# Wireless_Modular_Burn_Board.net
KiCad netlist of a schematic drawn in EAGLE
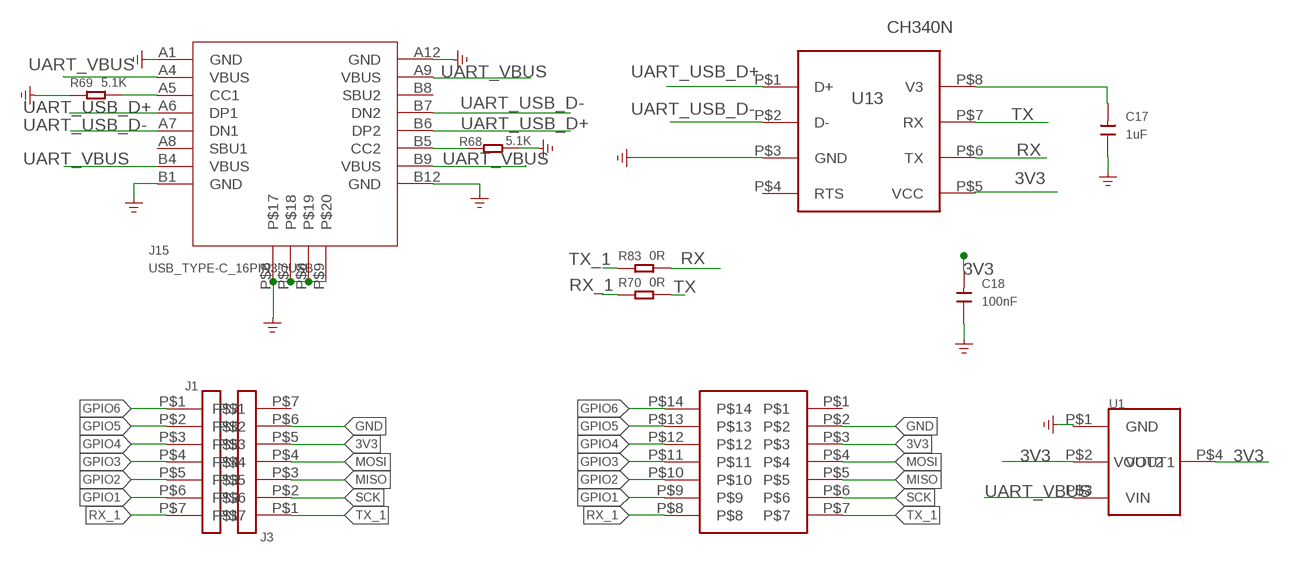
[diagram p0: schematic, sheet 1]

(export (version "E")
  (design (tool "Eeschema 10.0.6"))
  (components
    (comp (ref "C17")
      (value "1uF")
      (footprint "eagle-import:0603")
      (libsource (lib "eagle-import") (part "C0603"))
    )
    (comp (ref "C18")
      (value "100nF")
      (footprint "eagle-import:0603")
      (libsource (lib "eagle-import") (part "C0603"))
    )
    (comp (ref "J1")
      (value "2.54MM-7P")
      (footprint "eagle-import:2.54MM-7P")
      (libsource (lib "eagle-import") (part "2.54MM-7P"))
    )
    (comp (ref "J2")
      (value "SMT-2.54MM-7P")
      (footprint "eagle-import:SMT-2.54MM-7P")
      (libsource (lib "eagle-import") (part "SMT-2.54MM-7P"))
    )
    (comp (ref "J3")
      (value "2.54MM-7P")
      (footprint "eagle-import:2.54MM-7P")
      (libsource (lib "eagle-import") (part "2.54MM-7P"))
    )
    (comp (ref "J15")
      (value "USB_TYPE-C_16PIN3.0USB")
      (footprint "eagle-import:KEVIN_3.0TYPEC-SMD")
      (libsource (lib "eagle-import") (part "USB_TYPE-C_16PIN3.0USB"))
    )
    (comp (ref "R68")
      (value "5.1K")
      (footprint "eagle-import:DISCRETE_R0603")
      (libsource (lib "eagle-import") (part "DISCRETE_R-0603"))
    )
    (comp (ref "R69")
      (value "5.1K")
      (footprint "eagle-import:DISCRETE_R0603")
      (libsource (lib "eagle-import") (part "DISCRETE_R-0603"))
    )
    (comp (ref "R70")
      (value "0R")
      (footprint "eagle-import:DISCRETE_R0603")
      (libsource (lib "eagle-import") (part "DISCRETE_R-0603"))
    )
    (comp (ref "R83")
      (value "0R")
      (footprint "eagle-import:DISCRETE_R0603")
      (libsource (lib "eagle-import") (part "DISCRETE_R-0603"))
    )
    (comp (ref "U1")
      (value "AMS1117-3V3")
      (footprint "eagle-import:SOT-223")
      (libsource (lib "eagle-import") (part "AMS1117-3V3"))
    )
    (comp (ref "U13")
      (value "CH340N")
      (footprint "eagle-import:SOP8")
      (libsource (lib "eagle-import") (part "CH340NSOP-8"))
    )
  )
  (nets
    (net (code "1") (name "/RX") (class "Default")
      (node (ref "R83") (pin "2") (pinfunction "2_2") (pintype "passive"))
      (node (ref "U13") (pin "P$6") (pinfunction "TX_P$6") (pintype "bidirectional"))
    )
    (net (code "2") (name "/TX") (class "Default")
      (node (ref "R70") (pin "2") (pinfunction "2_2") (pintype "passive"))
      (node (ref "U13") (pin "P$7") (pinfunction "RX_P$7") (pintype "bidirectional"))
    )
    (net (code "3") (name "/UART_USB_D+") (class "Default")
      (node (ref "J15") (pin "A6") (pinfunction "DP1_A6") (pintype "bidirectional"))
      (node (ref "J15") (pin "B6") (pinfunction "DP2_B6") (pintype "bidirectional"))
      (node (ref "U13") (pin "P$1") (pinfunction "D+_P$1") (pintype "bidirectional"))
    )
    (net (code "4") (name "/UART_USB_D-") (class "Default")
      (node (ref "J15") (pin "A7") (pinfunction "DN1_A7") (pintype "bidirectional"))
      (node (ref "J15") (pin "B7") (pinfunction "DN2_B7") (pintype "bidirectional"))
      (node (ref "U13") (pin "P$2") (pinfunction "D-_P$2") (pintype "bidirectional"))
    )
    (net (code "5") (name "/UART_VBUS") (class "Default")
      (node (ref "J15") (pin "A4") (pinfunction "VBUS_A4") (pintype "bidirectional"))
      (node (ref "J15") (pin "A9") (pinfunction "VBUS_A9") (pintype "bidirectional"))
      (node (ref "J15") (pin "B4") (pinfunction "VBUS_B4") (pintype "bidirectional"))
      (node (ref "J15") (pin "B9") (pinfunction "VBUS_B9") (pintype "bidirectional"))
      (node (ref "U1") (pin "P$3") (pinfunction "VIN_P$3") (pintype "bidirectional"))
    )
    (net (code "6") (name "3V3") (class "Default")
      (node (ref "C18") (pin "2") (pinfunction "2_2") (pintype "passive"))
      (node (ref "J2") (pin "P$3") (pinfunction "P$3_P$3") (pintype "bidirectional"))
      (node (ref "J3") (pin "P$5") (pinfunction "P$5_P$5") (pintype "bidirectional"))
      (node (ref "U1") (pin "P$2") (pinfunction "VOUT1_P$2") (pintype "bidirectional"))
      (node (ref "U1") (pin "P$4") (pinfunction "VOUT2_P$4") (pintype "bidirectional"))
      (node (ref "U13") (pin "P$5") (pinfunction "VCC_P$5") (pintype "bidirectional"))
    )
    (net (code "7") (name "GND") (class "Default")
      (node (ref "C17") (pin "1") (pinfunction "1_1") (pintype "passive"))
      (node (ref "C18") (pin "1") (pinfunction "1_1") (pintype "passive"))
      (node (ref "J15") (pin "A1") (pinfunction "GND_A1") (pintype "bidirectional"))
      (node (ref "J15") (pin "A12") (pinfunction "GND_A12") (pintype "bidirectional"))
      (node (ref "J15") (pin "B1") (pinfunction "GND_B1") (pintype "bidirectional"))
      (node (ref "J15") (pin "B12") (pinfunction "GND_B12") (pintype "bidirectional"))
      (node (ref "J15") (pin "P$6") (pinfunction "P$17_P$6") (pintype "bidirectional"))
      (node (ref "J15") (pin "P$7") (pinfunction "P$18_P$7") (pintype "bidirectional"))
      (node (ref "J15") (pin "P$8") (pinfunction "P$19_P$8") (pintype "bidirectional"))
      (node (ref "J15") (pin "P$9") (pinfunction "P$20_P$9") (pintype "bidirectional"))
      (node (ref "J2") (pin "P$2") (pinfunction "P$2_P$2") (pintype "bidirectional"))
      (node (ref "J3") (pin "P$6") (pinfunction "P$6_P$6") (pintype "bidirectional"))
      (node (ref "R68") (pin "2") (pinfunction "2_2") (pintype "passive"))
      (node (ref "R69") (pin "1") (pinfunction "1_1") (pintype "passive"))
      (node (ref "U1") (pin "P$1") (pinfunction "GND_P$1") (pintype "bidirectional"))
      (node (ref "U13") (pin "P$3") (pinfunction "GND_P$3") (pintype "bidirectional"))
    )
    (net (code "8") (name "GPIO1") (class "Default")
      (node (ref "J1") (pin "P$6") (pinfunction "P$6_P$6") (pintype "bidirectional"))
      (node (ref "J2") (pin "P$9") (pinfunction "P$9_P$9") (pintype "bidirectional"))
    )
    (net (code "9") (name "GPIO2") (class "Default")
      (node (ref "J1") (pin "P$5") (pinfunction "P$5_P$5") (pintype "bidirectional"))
      (node (ref "J2") (pin "P$10") (pinfunction "P$10_P$10") (pintype "bidirectional"))
    )
    (net (code "10") (name "GPIO3") (class "Default")
      (node (ref "J1") (pin "P$4") (pinfunction "P$4_P$4") (pintype "bidirectional"))
      (node (ref "J2") (pin "P$11") (pinfunction "P$11_P$11") (pintype "bidirectional"))
    )
    (net (code "11") (name "GPIO4") (class "Default")
      (node (ref "J1") (pin "P$3") (pinfunction "P$3_P$3") (pintype "bidirectional"))
      (node (ref "J2") (pin "P$12") (pinfunction "P$12_P$12") (pintype "bidirectional"))
    )
    (net (code "12") (name "GPIO5") (class "Default")
      (node (ref "J1") (pin "P$2") (pinfunction "P$2_P$2") (pintype "bidirectional"))
      (node (ref "J2") (pin "P$13") (pinfunction "P$13_P$13") (pintype "bidirectional"))
    )
    (net (code "13") (name "GPIO6") (class "Default")
      (node (ref "J1") (pin "P$1") (pinfunction "P$1_P$1") (pintype "bidirectional"))
      (node (ref "J2") (pin "P$14") (pinfunction "P$14_P$14") (pintype "bidirectional"))
    )
    (net (code "14") (name "MISO") (class "Default")
      (node (ref "J2") (pin "P$5") (pinfunction "P$5_P$5") (pintype "bidirectional"))
      (node (ref "J3") (pin "P$3") (pinfunction "P$3_P$3") (pintype "bidirectional"))
    )
    (net (code "15") (name "MOSI") (class "Default")
      (node (ref "J2") (pin "P$4") (pinfunction "P$4_P$4") (pintype "bidirectional"))
      (node (ref "J3") (pin "P$4") (pinfunction "P$4_P$4") (pintype "bidirectional"))
    )
    (net (code "16") (name "Net-(J15-CC1)") (class "Default")
      (node (ref "J15") (pin "A5") (pinfunction "CC1_A5") (pintype "bidirectional"))
      (node (ref "R69") (pin "2") (pinfunction "2_2") (pintype "passive"))
    )
    (net (code "17") (name "Net-(J15-CC2)") (class "Default")
      (node (ref "J15") (pin "B5") (pinfunction "CC2_B5") (pintype "bidirectional"))
      (node (ref "R68") (pin "1") (pinfunction "1_1") (pintype "passive"))
    )
    (net (code "18") (name "Net-(U13-V3)") (class "Default")
      (node (ref "C17") (pin "2") (pinfunction "2_2") (pintype "passive"))
      (node (ref "U13") (pin "P$8") (pinfunction "V3_P$8") (pintype "bidirectional"))
    )
    (net (code "19") (name "RX_1") (class "Default")
      (node (ref "J1") (pin "P$7") (pinfunction "P$7_P$7") (pintype "bidirectional"))
      (node (ref "J2") (pin "P$8") (pinfunction "P$8_P$8") (pintype "bidirectional"))
      (node (ref "R70") (pin "1") (pinfunction "1_1") (pintype "passive"))
    )
    (net (code "20") (name "SCK") (class "Default")
      (node (ref "J2") (pin "P$6") (pinfunction "P$6_P$6") (pintype "bidirectional"))
      (node (ref "J3") (pin "P$2") (pinfunction "P$2_P$2") (pintype "bidirectional"))
    )
    (net (code "21") (name "TX_1") (class "Default")
      (node (ref "J2") (pin "P$7") (pinfunction "P$7_P$7") (pintype "bidirectional"))
      (node (ref "J3") (pin "P$1") (pinfunction "P$1_P$1") (pintype "bidirectional"))
      (node (ref "R83") (pin "1") (pinfunction "1_1") (pintype "passive"))
    )
    (net (code "22") (name "unconnected-(J2-PadP$1)") (class "Default")
      (node (ref "J2") (pin "P$1") (pinfunction "P$1_P$1") (pintype "bidirectional"))
    )
    (net (code "23") (name "unconnected-(J3-PadP$7)") (class "Default")
      (node (ref "J3") (pin "P$7") (pinfunction "P$7_P$7") (pintype "bidirectional"))
    )
    (net (code "24") (name "unconnected-(J15-SBU1-PadA8)") (class "Default")
      (node (ref "J15") (pin "A8") (pinfunction "SBU1_A8") (pintype "bidirectional"))
    )
    (net (code "25") (name "unconnected-(J15-SBU2-PadB8)") (class "Default")
      (node (ref "J15") (pin "B8") (pinfunction "SBU2_B8") (pintype "bidirectional"))
    )
    (net (code "26") (name "unconnected-(U13-RTS-PadP$4)") (class "Default")
      (node (ref "U13") (pin "P$4") (pinfunction "RTS_P$4") (pintype "bidirectional"))
    )
  )
)
